# 04_-FT601_USB_Tx_Rx_Interface.net
KiCad netlist of a schematic drawn in Altium Designer
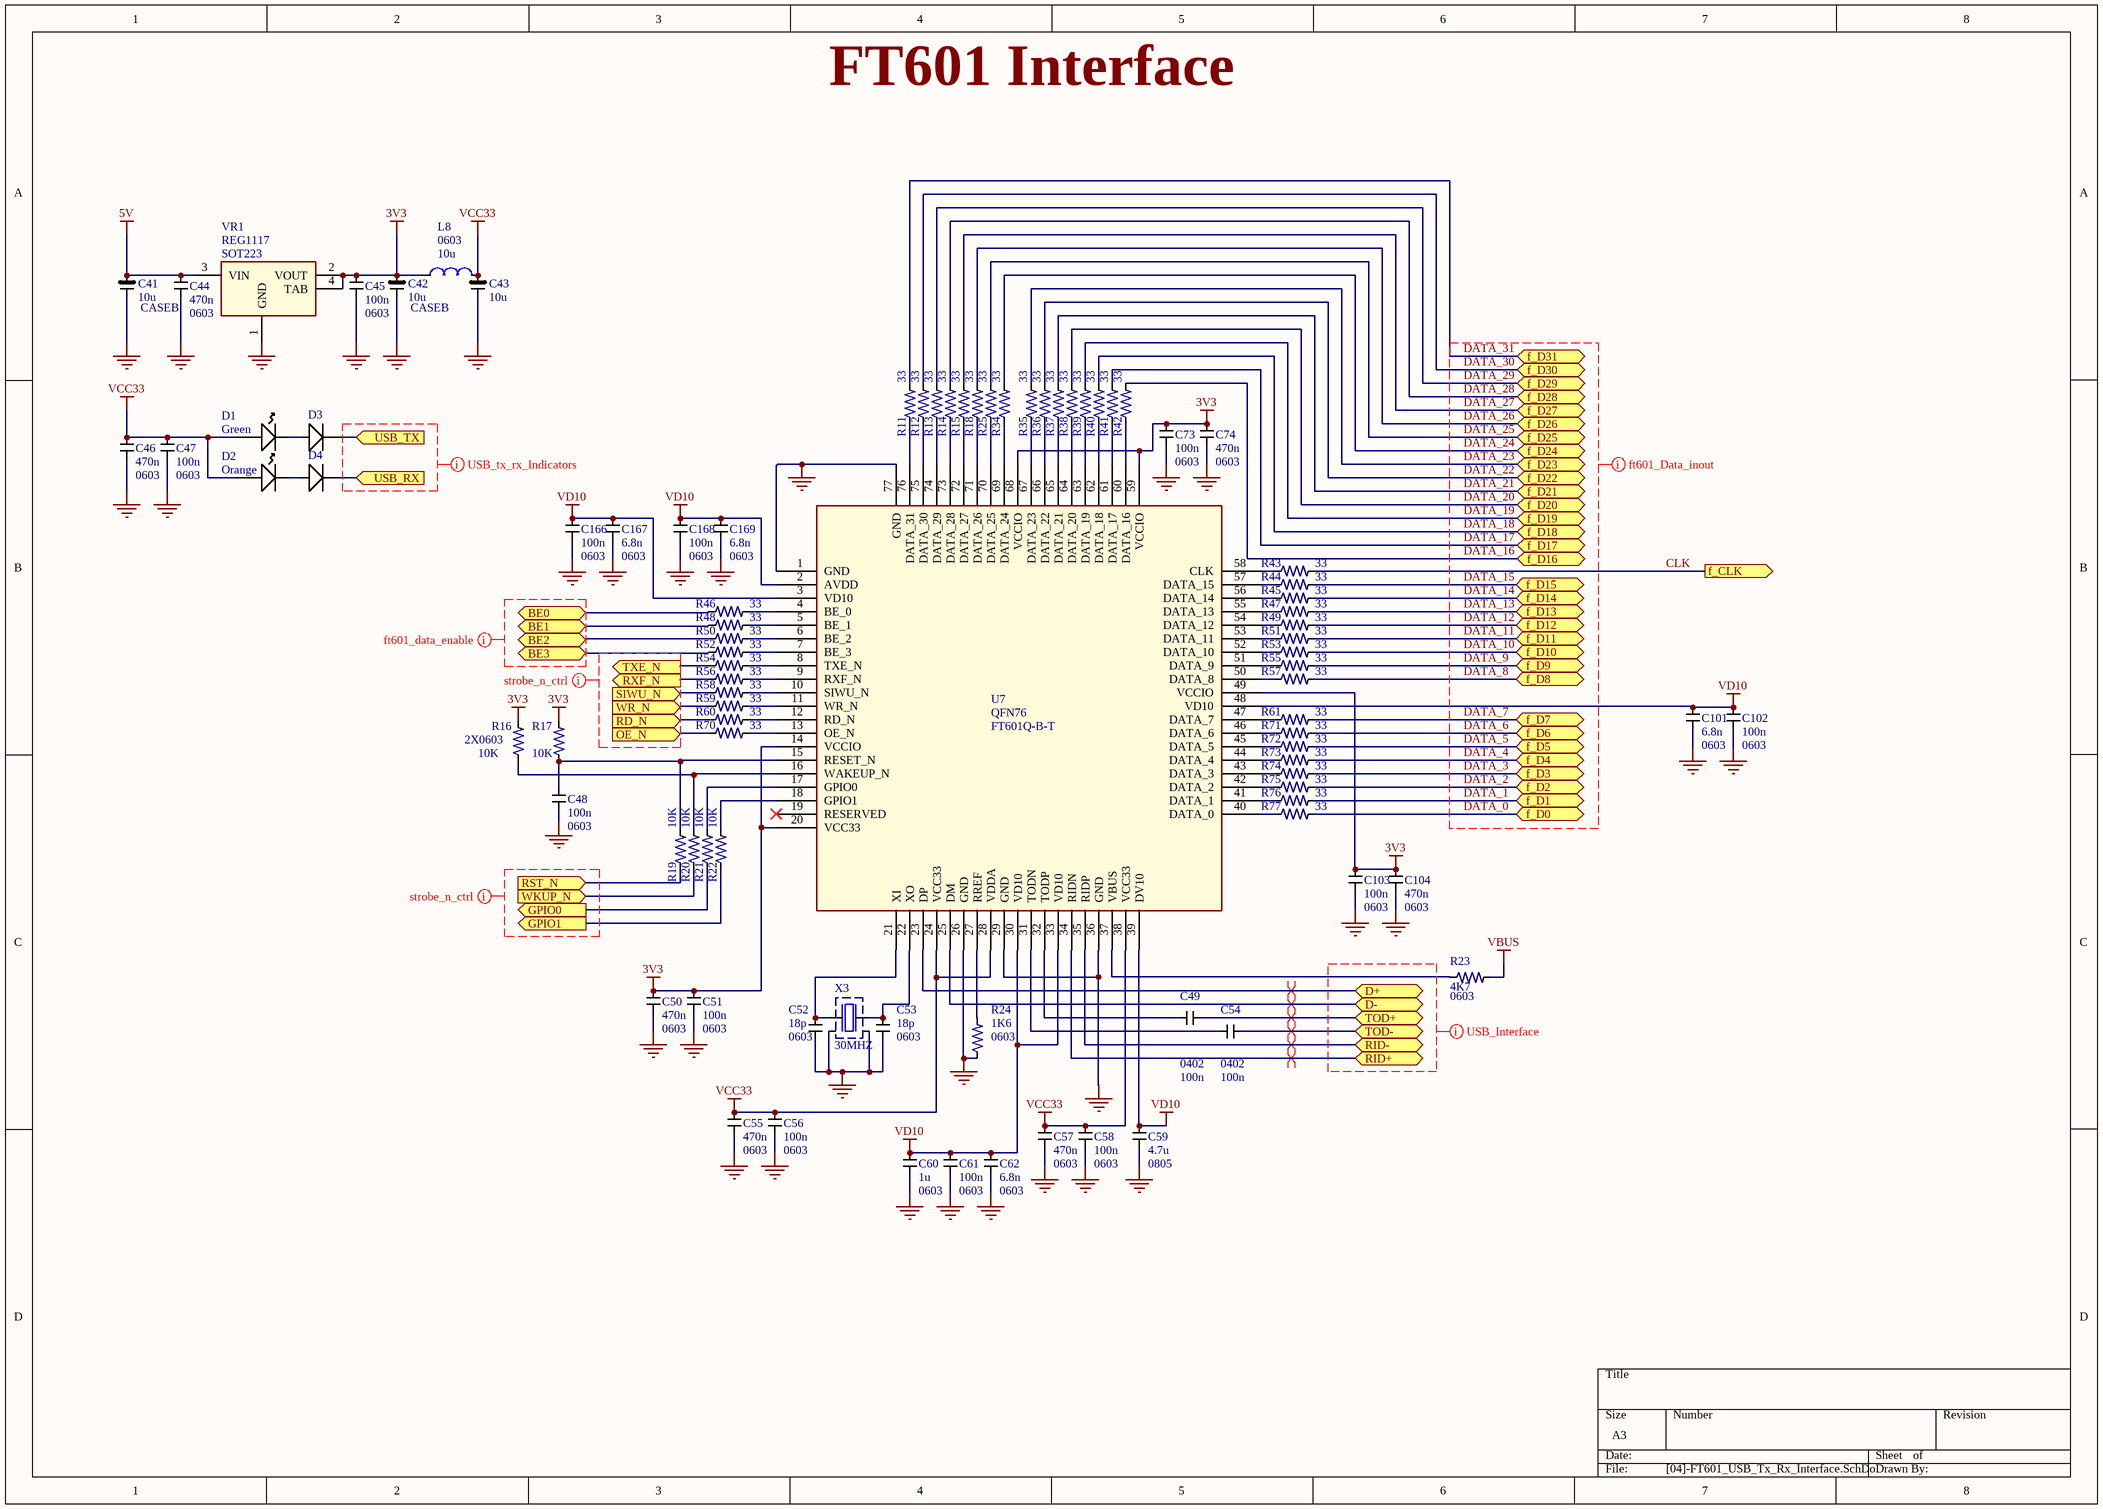
[diagram p0: [04]-FT601_USB_Tx_Rx_Interface.SchDoc]

(export (version "E")
  (design (tool "Eeschema 10.0.6"))
  (components
    (comp (ref "C41")
      (value "10u")
      (footprint "CAPC3528X21N")
      (fields (field (name "PCB LAYER") "CASEB"))
      (libsource (lib "T495B106K010ATE600") (part "Component_1"))
    )
    (comp (ref "C42")
      (value "10u")
      (footprint "CAPC3528X21N")
      (fields (field (name "PCB LAYER") "CASEB"))
      (libsource (lib "T495B106K010ATE600") (part "Component_1"))
    )
    (comp (ref "C43")
      (value "10u")
      (footprint "CAPC3528X21N")
      (libsource (lib "T495B106K010ATE600") (part "Component_1"))
    )
    (comp (ref "C44")
      (value "470n")
      (fields (field (name "PCB FOOTPRINT") "0603"))
      (libsource (lib "06031C104KAT2A") (part "Component_1"))
    )
    (comp (ref "C45")
      (value "100n")
      (fields (field (name "PCB FOOTPRINT") "0603"))
      (libsource (lib "06031C104KAT2A") (part "Component_1"))
    )
    (comp (ref "C46")
      (value "470n")
      (fields (field (name "PCB FOOTPRINT") "0603"))
      (libsource (lib "06031C104KAT2A") (part "Component_1"))
    )
    (comp (ref "C47")
      (value "100n")
      (fields (field (name "PCB FOOTPRINT") "0603"))
      (libsource (lib "06031C104KAT2A") (part "Component_1"))
    )
    (comp (ref "C48")
      (value "100n")
      (fields (field (name "PCB FOOTPRINT") "0603"))
      (libsource (lib "06031C104KAT2A") (part "Component_1"))
    )
    (comp (ref "C49")
      (value "100n")
      (footprint "*CAPC1005X60N")
      (fields (field (name "PCB STAKE") "0402"))
      (libsource (lib "04023C104KAT2A_0402") (part "Component_1"))
    )
    (comp (ref "C50")
      (value "470n")
      (fields (field (name "PCB FOOTPRINT") "0603"))
      (libsource (lib "06031C104KAT2A") (part "Component_1"))
    )
    (comp (ref "C51")
      (value "100n")
      (fields (field (name "PCB FOOTPRINT") "0603"))
      (libsource (lib "06031C104KAT2A") (part "Component_1"))
    )
    (comp (ref "C52")
      (value "18p")
      (footprint "*CAPC1608X90")
      (fields (field (name "PCB LAYOUT:") "0603"))
      (libsource (lib "06032U180GAT2A") (part "Component_1"))
    )
    (comp (ref "C53")
      (value "18p")
      (footprint "*CAPC1608X90")
      (fields (field (name "PCB LAYOUT:") "0603"))
      (libsource (lib "06032U180GAT2A") (part "Component_1"))
    )
    (comp (ref "C54")
      (value "100n")
      (footprint "*CAPC1005X60N")
      (fields (field (name "PCB STAKE") "0402"))
      (libsource (lib "04023C104KAT2A_0402") (part "Component_1"))
    )
    (comp (ref "C55")
      (value "470n")
      (fields (field (name "PCB FOOTPRINT") "0603"))
      (libsource (lib "06031C104KAT2A") (part "Component_1"))
    )
    (comp (ref "C56")
      (value "100n")
      (fields (field (name "PCB FOOTPRINT") "0603"))
      (libsource (lib "06031C104KAT2A") (part "Component_1"))
    )
    (comp (ref "C57")
      (value "470n")
      (fields (field (name "PCB FOOTPRINT") "0603"))
      (libsource (lib "06031C104KAT2A") (part "Component_1"))
    )
    (comp (ref "C58")
      (value "100n")
      (fields (field (name "PCB FOOTPRINT") "0603"))
      (libsource (lib "06031C104KAT2A") (part "Component_1"))
    )
    (comp (ref "C59")
      (value "4.7u")
      (footprint "*CAPC2013X140N")
      (fields (field (name "PCB PACKAGE") "0805"))
      (libsource (lib "08053D475KAT2A") (part "Component_1"))
    )
    (comp (ref "C60")
      (value "1u")
      (fields (field (name "PCB FOOTPRINT") "0603"))
      (libsource (lib "06031C104KAT2A") (part "Component_1"))
    )
    (comp (ref "C61")
      (value "100n")
      (footprint "CAPC1608X10N")
      (fields (field (name "PCB PACKAGE") "0603"))
      (libsource (lib "MC0603B682K500CT") (part "Component_1"))
    )
    (comp (ref "C62")
      (value "6.8n")
      (footprint "*0603")
      (fields (field (name "PCB LAYER:") "0603"))
      (libsource (lib "0603YC105KAT2A") (part "Component_1"))
    )
    (comp (ref "C73")
      (value "100n")
      (fields (field (name "PCB FOOTPRINT") "0603"))
      (libsource (lib "06031C104KAT2A") (part "Component_1"))
    )
    (comp (ref "C74")
      (value "470n")
      (fields (field (name "PCB FOOTPRINT") "0603"))
      (libsource (lib "06031C104KAT2A") (part "Component_1"))
    )
    (comp (ref "C101")
      (value "6.8n")
      (footprint "CAPC1608X10N")
      (fields (field (name "PCB PACKAGE") "0603"))
      (libsource (lib "MC0603B682K500CT") (part "Component_1"))
    )
    (comp (ref "C102")
      (value "100n")
      (fields (field (name "PCB FOOTPRINT") "0603"))
      (libsource (lib "06031C104KAT2A") (part "Component_1"))
    )
    (comp (ref "C103")
      (value "100n")
      (fields (field (name "PCB FOOTPRINT") "0603"))
      (libsource (lib "06031C104KAT2A") (part "Component_1"))
    )
    (comp (ref "C104")
      (value "470n")
      (fields (field (name "PCB FOOTPRINT") "0603"))
      (libsource (lib "06031C104KAT2A") (part "Component_1"))
    )
    (comp (ref "C166")
      (value "100n")
      (fields (field (name "PCB FOOTPRINT") "0603"))
      (libsource (lib "06031C104KAT2A") (part "Component_1"))
    )
    (comp (ref "C167")
      (value "6.8n")
      (fields (field (name "PCB FOOTPRINT") "0603"))
      (libsource (lib "06031C104KAT2A") (part "Component_1"))
    )
    (comp (ref "C168")
      (value "100n")
      (fields (field (name "PCB FOOTPRINT") "0603"))
      (libsource (lib "06031C104KAT2A") (part "Component_1"))
    )
    (comp (ref "C169")
      (value "6.8n")
      (fields (field (name "PCB FOOTPRINT") "0603"))
      (libsource (lib "06031C104KAT2A") (part "Component_1"))
    )
    (comp (ref "D1")
      (value "Kingbright Green LED, 70 mcd 120 ° 0805")
      (footprint "LED1913X12NGREEN")
      (fields
        (field (name "MANUFACTURER") "KingBright")
        (field (name "MANUFACTURER PART NO.") "KP-2012MGC")
        (field (name "COLOR") "Green")
        (field (name "CREATOR") "Ritesh Kanjee")
      )
      (libsource (lib "KingBright LEDs") (part "Kingbright Green LED, 70 mcd 120 ° 0805"))
    )
    (comp (ref "D2")
      (value "Kingbright Orange LED, 200 mcd 120 ° 0805")
      (footprint "LED1913X12NYEL/ORANGE")
      (fields
        (field (name "MANUFACTURER") "KingBright")
        (field (name "MANUFACTURER PART NO.") "KP-2012SEC")
        (field (name "COLOR") "Orange")
        (field (name "CREATOR") "Ritesh Kanjee")
      )
      (libsource (lib "KingBright LEDs") (part "Kingbright Orange LED, 200 mcd 120 ° 0805"))
    )
    (comp (ref "D3")
      (value "Panasonic DB2J20900L Schottky Diode, 0.5A, 20V, 2.4ns, 2-Pin SMini2 F5 B")
      (footprint "DIOM1712X07N")
      (fields
        (field (name "MANUFACTURER") "Panasonic")
        (field (name "MANUFACTURER PART NO.") "DB2J20900L")
        (field (name "CREATED BY") "R Kanjee")
      )
      (libsource (lib "Panasonic Diodes") (part "Schottky Diode, 0.5A, 20V, 2.4ns, 2-Pin SMini2 F5 B"))
    )
    (comp (ref "D4")
      (value "Panasonic DB2J20900L Schottky Diode, 0.5A, 20V, 2.4ns, 2-Pin SMini2 F5 B")
      (footprint "DIOM1712X07N")
      (fields
        (field (name "MANUFACTURER") "Panasonic")
        (field (name "MANUFACTURER PART NO.") "DB2J20900L")
        (field (name "CREATED BY") "R Kanjee")
      )
      (libsource (lib "Panasonic Diodes") (part "Schottky Diode, 0.5A, 20V, 2.4ns, 2-Pin SMini2 F5 B"))
    )
    (comp (ref "L8")
      (value "10u")
      (footprint "*INDC1608X95N")
      (fields (field (name "PCB LAYOUT:") "0603"))
      (libsource (lib "MLZ1608M100WTD25") (part "Component_1"))
    )
    (comp (ref "R11")
      (value "33")
      (footprint "*R0402")
      (description "Res Thin Film 0603 76.8 Ohm 0.1% 1/10W Â±15ppm/Â°C Molded SMD Paper T/R")
      (libsource (lib "SMD-RES-100K-1_-1_16W_0402_") (part "RP73D1J76R8BTDG"))
    )
    (comp (ref "R12")
      (value "33")
      (footprint "*R0402")
      (description "Res Thin Film 0603 76.8 Ohm 0.1% 1/10W Â±15ppm/Â°C Molded SMD Paper T/R")
      (libsource (lib "SMD-RES-100K-1_-1_16W_0402_") (part "RP73D1J76R8BTDG"))
    )
    (comp (ref "R13")
      (value "33")
      (footprint "*R0402")
      (description "Res Thin Film 0603 76.8 Ohm 0.1% 1/10W Â±15ppm/Â°C Molded SMD Paper T/R")
      (libsource (lib "SMD-RES-100K-1_-1_16W_0402_") (part "RP73D1J76R8BTDG"))
    )
    (comp (ref "R14")
      (value "33")
      (footprint "*R0402")
      (description "Res Thin Film 0603 76.8 Ohm 0.1% 1/10W Â±15ppm/Â°C Molded SMD Paper T/R")
      (libsource (lib "SMD-RES-100K-1_-1_16W_0402_") (part "RP73D1J76R8BTDG"))
    )
    (comp (ref "R15")
      (value "33")
      (footprint "*R0402")
      (description "Res Thin Film 0603 76.8 Ohm 0.1% 1/10W Â±15ppm/Â°C Molded SMD Paper T/R")
      (libsource (lib "SMD-RES-100K-1_-1_16W_0402_") (part "RP73D1J76R8BTDG"))
    )
    (comp (ref "R16")
      (value "10K")
      (footprint "*0603")
      (description "Res Thin Film 0603 76.8 Ohm 0.1% 1/10W Â±15ppm/Â°C Molded SMD Paper T/R")
      (fields
        (field (name "MP") "RP73D1J76R8BTDG")
        (field (name "MF") "TE Connectivity / Holsworthy")
        (field (name "FOOT PRINT") "2X0603")
      )
      (libsource (lib "CRCW060310K0FKEAHP") (part "RP73D1J76R8BTDG"))
    )
    (comp (ref "R17")
      (value "10K")
      (footprint "*0603")
      (description "Res Thin Film 0603 76.8 Ohm 0.1% 1/10W Â±15ppm/Â°C Molded SMD Paper T/R")
      (fields (field (name "MP") "RP73D1J76R8BTDG") (field (name "MF") "TE Connectivity / Holsworthy"))
      (libsource (lib "CRCW060310K0FKEAHP") (part "RP73D1J76R8BTDG"))
    )
    (comp (ref "R18")
      (value "33")
      (footprint "*R0402")
      (description "Res Thin Film 0603 76.8 Ohm 0.1% 1/10W Â±15ppm/Â°C Molded SMD Paper T/R")
      (libsource (lib "SMD-RES-100K-1_-1_16W_0402_") (part "RP73D1J76R8BTDG"))
    )
    (comp (ref "R19")
      (value "10K")
      (footprint "*0603")
      (description "Res Thin Film 0603 76.8 Ohm 0.1% 1/10W Â±15ppm/Â°C Molded SMD Paper T/R")
      (fields (field (name "MP") "RP73D1J76R8BTDG") (field (name "MF") "TE Connectivity / Holsworthy"))
      (libsource (lib "CRCW060310K0FKEAHP") (part "RP73D1J76R8BTDG"))
    )
    (comp (ref "R20")
      (value "10K")
      (footprint "*0603")
      (description "Res Thin Film 0603 76.8 Ohm 0.1% 1/10W Â±15ppm/Â°C Molded SMD Paper T/R")
      (fields (field (name "MP") "RP73D1J76R8BTDG") (field (name "MF") "TE Connectivity / Holsworthy"))
      (libsource (lib "CRCW060310K0FKEAHP") (part "RP73D1J76R8BTDG"))
    )
    (comp (ref "R21")
      (value "10K")
      (footprint "*0603")
      (description "Res Thin Film 0603 76.8 Ohm 0.1% 1/10W Â±15ppm/Â°C Molded SMD Paper T/R")
      (fields (field (name "MP") "RP73D1J76R8BTDG") (field (name "MF") "TE Connectivity / Holsworthy"))
      (libsource (lib "CRCW060310K0FKEAHP") (part "RP73D1J76R8BTDG"))
    )
    (comp (ref "R22")
      (value "10K")
      (footprint "*0603")
      (description "Res Thin Film 0603 76.8 Ohm 0.1% 1/10W Â±15ppm/Â°C Molded SMD Paper T/R")
      (fields (field (name "MP") "RP73D1J76R8BTDG") (field (name "MF") "TE Connectivity / Holsworthy"))
      (libsource (lib "CRCW060310K0FKEAHP") (part "RP73D1J76R8BTDG"))
    )
    (comp (ref "R23")
      (value "4K7")
      (footprint "*RESC1608X50N")
      (description "Res Thin Film 0603 76.8 Ohm 0.1% 1/10W Â±15ppm/Â°C Molded SMD Paper T/R")
      (fields
        (field (name "MP") "RP73D1J76R8BTDG")
        (field (name "MF") "TE Connectivity / Holsworthy")
        (field (name "FOOT PRINT") "0603")
      )
      (libsource (lib "CRGH0603F4K7") (part "RP73D1J76R8BTDG"))
    )
    (comp (ref "R24")
      (value "1K6")
      (footprint "*0603")
      (description "Res Thin Film 0603 76.8 Ohm 0.1% 1/10W Â±15ppm/Â°C Molded SMD Paper T/R")
      (fields
        (field (name "MP") "RP73D1J76R8BTDG")
        (field (name "MF") "TE Connectivity / Holsworthy")
        (field (name "FOOT PRINT") "0603")
      )
      (libsource (lib "CRCW060310K0FKEAHP") (part "RP73D1J76R8BTDG"))
    )
    (comp (ref "R25")
      (value "33")
      (footprint "*R0402")
      (description "Res Thin Film 0603 76.8 Ohm 0.1% 1/10W Â±15ppm/Â°C Molded SMD Paper T/R")
      (libsource (lib "SMD-RES-100K-1_-1_16W_0402_") (part "RP73D1J76R8BTDG"))
    )
    (comp (ref "R34")
      (value "33")
      (footprint "*R0402")
      (description "Res Thin Film 0603 76.8 Ohm 0.1% 1/10W Â±15ppm/Â°C Molded SMD Paper T/R")
      (libsource (lib "SMD-RES-100K-1_-1_16W_0402_") (part "RP73D1J76R8BTDG"))
    )
    (comp (ref "R35")
      (value "33")
      (footprint "*R0402")
      (description "Res Thin Film 0603 76.8 Ohm 0.1% 1/10W Â±15ppm/Â°C Molded SMD Paper T/R")
      (libsource (lib "SMD-RES-100K-1_-1_16W_0402_") (part "RP73D1J76R8BTDG"))
    )
    (comp (ref "R36")
      (value "33")
      (footprint "*R0402")
      (description "Res Thin Film 0603 76.8 Ohm 0.1% 1/10W Â±15ppm/Â°C Molded SMD Paper T/R")
      (libsource (lib "SMD-RES-100K-1_-1_16W_0402_") (part "RP73D1J76R8BTDG"))
    )
    (comp (ref "R37")
      (value "33")
      (footprint "*R0402")
      (description "Res Thin Film 0603 76.8 Ohm 0.1% 1/10W Â±15ppm/Â°C Molded SMD Paper T/R")
      (libsource (lib "SMD-RES-100K-1_-1_16W_0402_") (part "RP73D1J76R8BTDG"))
    )
    (comp (ref "R38")
      (value "33")
      (footprint "*R0402")
      (description "Res Thin Film 0603 76.8 Ohm 0.1% 1/10W Â±15ppm/Â°C Molded SMD Paper T/R")
      (libsource (lib "SMD-RES-100K-1_-1_16W_0402_") (part "RP73D1J76R8BTDG"))
    )
    (comp (ref "R39")
      (value "33")
      (footprint "*R0402")
      (description "Res Thin Film 0603 76.8 Ohm 0.1% 1/10W Â±15ppm/Â°C Molded SMD Paper T/R")
      (libsource (lib "SMD-RES-100K-1_-1_16W_0402_") (part "RP73D1J76R8BTDG"))
    )
    (comp (ref "R40")
      (value "33")
      (footprint "*R0402")
      (description "Res Thin Film 0603 76.8 Ohm 0.1% 1/10W Â±15ppm/Â°C Molded SMD Paper T/R")
      (libsource (lib "SMD-RES-100K-1_-1_16W_0402_") (part "RP73D1J76R8BTDG"))
    )
    (comp (ref "R41")
      (value "33")
      (footprint "*R0402")
      (description "Res Thin Film 0603 76.8 Ohm 0.1% 1/10W Â±15ppm/Â°C Molded SMD Paper T/R")
      (libsource (lib "SMD-RES-100K-1_-1_16W_0402_") (part "RP73D1J76R8BTDG"))
    )
    (comp (ref "R42")
      (value "33")
      (footprint "*R0402")
      (description "Res Thin Film 0603 76.8 Ohm 0.1% 1/10W Â±15ppm/Â°C Molded SMD Paper T/R")
      (libsource (lib "SMD-RES-100K-1_-1_16W_0402_") (part "RP73D1J76R8BTDG"))
    )
    (comp (ref "R43")
      (value "33")
      (footprint "*R0402")
      (description "Res Thin Film 0603 76.8 Ohm 0.1% 1/10W Â±15ppm/Â°C Molded SMD Paper T/R")
      (libsource (lib "SMD-RES-100K-1_-1_16W_0402_") (part "RP73D1J76R8BTDG"))
    )
    (comp (ref "R44")
      (value "33")
      (footprint "*R0402")
      (description "Res Thin Film 0603 76.8 Ohm 0.1% 1/10W Â±15ppm/Â°C Molded SMD Paper T/R")
      (libsource (lib "SMD-RES-100K-1_-1_16W_0402_") (part "RP73D1J76R8BTDG"))
    )
    (comp (ref "R45")
      (value "33")
      (footprint "*R0402")
      (description "Res Thin Film 0603 76.8 Ohm 0.1% 1/10W Â±15ppm/Â°C Molded SMD Paper T/R")
      (libsource (lib "SMD-RES-100K-1_-1_16W_0402_") (part "RP73D1J76R8BTDG"))
    )
    (comp (ref "R46")
      (value "33")
      (footprint "*R0402")
      (description "Res Thin Film 0603 76.8 Ohm 0.1% 1/10W Â±15ppm/Â°C Molded SMD Paper T/R")
      (libsource (lib "SMD-RES-100K-1_-1_16W_0402_") (part "RP73D1J76R8BTDG"))
    )
    (comp (ref "R47")
      (value "33")
      (footprint "*R0402")
      (description "Res Thin Film 0603 76.8 Ohm 0.1% 1/10W Â±15ppm/Â°C Molded SMD Paper T/R")
      (libsource (lib "SMD-RES-100K-1_-1_16W_0402_") (part "RP73D1J76R8BTDG"))
    )
    (comp (ref "R48")
      (value "33")
      (footprint "*R0402")
      (description "Res Thin Film 0603 76.8 Ohm 0.1% 1/10W Â±15ppm/Â°C Molded SMD Paper T/R")
      (libsource (lib "SMD-RES-100K-1_-1_16W_0402_") (part "RP73D1J76R8BTDG"))
    )
    (comp (ref "R49")
      (value "33")
      (footprint "*R0402")
      (description "Res Thin Film 0603 76.8 Ohm 0.1% 1/10W Â±15ppm/Â°C Molded SMD Paper T/R")
      (libsource (lib "SMD-RES-100K-1_-1_16W_0402_") (part "RP73D1J76R8BTDG"))
    )
    (comp (ref "R50")
      (value "33")
      (footprint "*R0402")
      (description "Res Thin Film 0603 76.8 Ohm 0.1% 1/10W Â±15ppm/Â°C Molded SMD Paper T/R")
      (libsource (lib "SMD-RES-100K-1_-1_16W_0402_") (part "RP73D1J76R8BTDG"))
    )
    (comp (ref "R51")
      (value "33")
      (footprint "*R0402")
      (description "Res Thin Film 0603 76.8 Ohm 0.1% 1/10W Â±15ppm/Â°C Molded SMD Paper T/R")
      (libsource (lib "SMD-RES-100K-1_-1_16W_0402_") (part "RP73D1J76R8BTDG"))
    )
    (comp (ref "R52")
      (value "33")
      (footprint "*R0402")
      (description "Res Thin Film 0603 76.8 Ohm 0.1% 1/10W Â±15ppm/Â°C Molded SMD Paper T/R")
      (libsource (lib "SMD-RES-100K-1_-1_16W_0402_") (part "RP73D1J76R8BTDG"))
    )
    (comp (ref "R53")
      (value "33")
      (footprint "*R0402")
      (description "Res Thin Film 0603 76.8 Ohm 0.1% 1/10W Â±15ppm/Â°C Molded SMD Paper T/R")
      (libsource (lib "SMD-RES-100K-1_-1_16W_0402_") (part "RP73D1J76R8BTDG"))
    )
    (comp (ref "R54")
      (value "33")
      (footprint "*R0402")
      (description "Res Thin Film 0603 76.8 Ohm 0.1% 1/10W Â±15ppm/Â°C Molded SMD Paper T/R")
      (libsource (lib "SMD-RES-100K-1_-1_16W_0402_") (part "RP73D1J76R8BTDG"))
    )
    (comp (ref "R55")
      (value "33")
      (footprint "*R0402")
      (description "Res Thin Film 0603 76.8 Ohm 0.1% 1/10W Â±15ppm/Â°C Molded SMD Paper T/R")
      (libsource (lib "SMD-RES-100K-1_-1_16W_0402_") (part "RP73D1J76R8BTDG"))
    )
    (comp (ref "R56")
      (value "33")
      (footprint "*R0402")
      (description "Res Thin Film 0603 76.8 Ohm 0.1% 1/10W Â±15ppm/Â°C Molded SMD Paper T/R")
      (libsource (lib "SMD-RES-100K-1_-1_16W_0402_") (part "RP73D1J76R8BTDG"))
    )
    (comp (ref "R57")
      (value "33")
      (footprint "*R0402")
      (description "Res Thin Film 0603 76.8 Ohm 0.1% 1/10W Â±15ppm/Â°C Molded SMD Paper T/R")
      (libsource (lib "SMD-RES-100K-1_-1_16W_0402_") (part "RP73D1J76R8BTDG"))
    )
    (comp (ref "R58")
      (value "33")
      (footprint "*R0402")
      (description "Res Thin Film 0603 76.8 Ohm 0.1% 1/10W Â±15ppm/Â°C Molded SMD Paper T/R")
      (libsource (lib "SMD-RES-100K-1_-1_16W_0402_") (part "RP73D1J76R8BTDG"))
    )
    (comp (ref "R59")
      (value "33")
      (footprint "*R0402")
      (description "Res Thin Film 0603 76.8 Ohm 0.1% 1/10W Â±15ppm/Â°C Molded SMD Paper T/R")
      (libsource (lib "SMD-RES-100K-1_-1_16W_0402_") (part "RP73D1J76R8BTDG"))
    )
    (comp (ref "R60")
      (value "33")
      (footprint "*R0402")
      (description "Res Thin Film 0603 76.8 Ohm 0.1% 1/10W Â±15ppm/Â°C Molded SMD Paper T/R")
      (libsource (lib "SMD-RES-100K-1_-1_16W_0402_") (part "RP73D1J76R8BTDG"))
    )
    (comp (ref "R61")
      (value "33")
      (footprint "*R0402")
      (description "Res Thin Film 0603 76.8 Ohm 0.1% 1/10W Â±15ppm/Â°C Molded SMD Paper T/R")
      (libsource (lib "SMD-RES-100K-1_-1_16W_0402_") (part "RP73D1J76R8BTDG"))
    )
    (comp (ref "R70")
      (value "33")
      (footprint "*R0402")
      (description "Res Thin Film 0603 76.8 Ohm 0.1% 1/10W Â±15ppm/Â°C Molded SMD Paper T/R")
      (libsource (lib "SMD-RES-100K-1_-1_16W_0402_") (part "RP73D1J76R8BTDG"))
    )
    (comp (ref "R71")
      (value "33")
      (footprint "*R0402")
      (description "Res Thin Film 0603 76.8 Ohm 0.1% 1/10W Â±15ppm/Â°C Molded SMD Paper T/R")
      (libsource (lib "SMD-RES-100K-1_-1_16W_0402_") (part "RP73D1J76R8BTDG"))
    )
    (comp (ref "R72")
      (value "33")
      (footprint "*R0402")
      (description "Res Thin Film 0603 76.8 Ohm 0.1% 1/10W Â±15ppm/Â°C Molded SMD Paper T/R")
      (libsource (lib "SMD-RES-100K-1_-1_16W_0402_") (part "RP73D1J76R8BTDG"))
    )
    (comp (ref "R73")
      (value "33")
      (footprint "*R0402")
      (description "Res Thin Film 0603 76.8 Ohm 0.1% 1/10W Â±15ppm/Â°C Molded SMD Paper T/R")
      (libsource (lib "SMD-RES-100K-1_-1_16W_0402_") (part "RP73D1J76R8BTDG"))
    )
    (comp (ref "R74")
      (value "33")
      (footprint "*R0402")
      (description "Res Thin Film 0603 76.8 Ohm 0.1% 1/10W Â±15ppm/Â°C Molded SMD Paper T/R")
      (libsource (lib "SMD-RES-100K-1_-1_16W_0402_") (part "RP73D1J76R8BTDG"))
    )
    (comp (ref "R75")
      (value "33")
      (footprint "*R0402")
      (description "Res Thin Film 0603 76.8 Ohm 0.1% 1/10W Â±15ppm/Â°C Molded SMD Paper T/R")
      (libsource (lib "SMD-RES-100K-1_-1_16W_0402_") (part "RP73D1J76R8BTDG"))
    )
    (comp (ref "R76")
      (value "33")
      (footprint "*R0402")
      (description "Res Thin Film 0603 76.8 Ohm 0.1% 1/10W Â±15ppm/Â°C Molded SMD Paper T/R")
      (libsource (lib "SMD-RES-100K-1_-1_16W_0402_") (part "RP73D1J76R8BTDG"))
    )
    (comp (ref "R77")
      (value "33")
      (footprint "*R0402")
      (description "Res Thin Film 0603 76.8 Ohm 0.1% 1/10W Â±15ppm/Â°C Molded SMD Paper T/R")
      (libsource (lib "SMD-RES-100K-1_-1_16W_0402_") (part "RP73D1J76R8BTDG"))
    )
    (comp (ref "U7")
      (value "FT601Q-B-T")
      (footprint "QFN40P900X900X100-77N")
      (description "USB3.0 to 32bit FIFO Interface Bridge QFN76 Tray")
      (fields
        (field (name "PACKAGE TYPE:") "QFN76")
        (field (name "DESIGNER") "Faheem Minhas")
        (field (name "DATA CREATED") "21-Janruary-2019")
      )
      (libsource (lib "FT601Q-B-T") (part "FT601Q-B-T"))
    )
    (comp (ref "VR1")
      (value "REG1117")
      (footprint "*SOT223")
      (description "LDO Regulator Pos 1.25V to 13.5V 0.8A 4-Pin_3+Tab_ SOT-223 Tube")
      (fields
        (field (name "MF") "Texas Instruments")
        (field (name "DIGI-KEY_PART_NUMBER") "REG1117-ND")
        (field (name "PCB LAYOUT:") "SOT223")
      )
      (libsource (lib "REG1117") (part "REG1117"))
    )
    (comp (ref "X3")
      (value "30MHZ")
      (footprint "OSC_DSC6083CI2A-032K768")
      (fields (field (name "MF") "ABM8G-30.000MHZ-18-D2Y-T"))
      (libsource (lib "ABM8G-30.000MHZ-18-D2Y-T") (part "Component_1"))
    )
  )
  (nets
    (net (code "1") (name "/BE0") (class "Default")
      (node (ref "R46") (pin "1") (pinfunction "1_1") (pintype "passive"))
    )
    (net (code "2") (name "/BE1") (class "Default")
      (node (ref "R48") (pin "1") (pinfunction "1_1") (pintype "passive"))
    )
    (net (code "3") (name "/BE2") (class "Default")
      (node (ref "R50") (pin "1") (pinfunction "1_1") (pintype "passive"))
    )
    (net (code "4") (name "/BE3") (class "Default")
      (node (ref "R52") (pin "1") (pinfunction "1_1") (pintype "passive"))
    )
    (net (code "5") (name "/CLK") (class "Default")
      (node (ref "R43") (pin "2") (pinfunction "2_2") (pintype "passive"))
    )
    (net (code "6") (name "/D+") (class "Default")
      (node (ref "U7") (pin "23") (pinfunction "DP_23") (pintype "passive"))
    )
    (net (code "7") (name "/D-") (class "Default")
      (node (ref "U7") (pin "25") (pinfunction "DM_25") (pintype "passive"))
    )
    (net (code "8") (name "/DATA_0") (class "Default")
      (node (ref "R77") (pin "2") (pinfunction "2_2") (pintype "passive"))
    )
    (net (code "9") (name "/DATA_1") (class "Default")
      (node (ref "R76") (pin "2") (pinfunction "2_2") (pintype "passive"))
    )
    (net (code "10") (name "/DATA_2") (class "Default")
      (node (ref "R75") (pin "2") (pinfunction "2_2") (pintype "passive"))
    )
    (net (code "11") (name "/DATA_3") (class "Default")
      (node (ref "R74") (pin "2") (pinfunction "2_2") (pintype "passive"))
    )
    (net (code "12") (name "/DATA_4") (class "Default")
      (node (ref "R73") (pin "2") (pinfunction "2_2") (pintype "passive"))
    )
    (net (code "13") (name "/DATA_5") (class "Default")
      (node (ref "R72") (pin "2") (pinfunction "2_2") (pintype "passive"))
    )
    (net (code "14") (name "/DATA_6") (class "Default")
      (node (ref "R71") (pin "2") (pinfunction "2_2") (pintype "passive"))
    )
    (net (code "15") (name "/DATA_7") (class "Default")
      (node (ref "R61") (pin "2") (pinfunction "2_2") (pintype "passive"))
    )
    (net (code "16") (name "/DATA_8") (class "Default")
      (node (ref "R57") (pin "2") (pinfunction "2_2") (pintype "passive"))
    )
    (net (code "17") (name "/DATA_9") (class "Default")
      (node (ref "R55") (pin "2") (pinfunction "2_2") (pintype "passive"))
    )
    (net (code "18") (name "/DATA_10") (class "Default")
      (node (ref "R53") (pin "2") (pinfunction "2_2") (pintype "passive"))
    )
    (net (code "19") (name "/DATA_11") (class "Default")
      (node (ref "R51") (pin "2") (pinfunction "2_2") (pintype "passive"))
    )
    (net (code "20") (name "/DATA_12") (class "Default")
      (node (ref "R49") (pin "2") (pinfunction "2_2") (pintype "passive"))
    )
    (net (code "21") (name "/DATA_13") (class "Default")
      (node (ref "R47") (pin "2") (pinfunction "2_2") (pintype "passive"))
    )
    (net (code "22") (name "/DATA_14") (class "Default")
      (node (ref "R45") (pin "2") (pinfunction "2_2") (pintype "passive"))
    )
    (net (code "23") (name "/DATA_15") (class "Default")
      (node (ref "R44") (pin "2") (pinfunction "2_2") (pintype "passive"))
    )
    (net (code "24") (name "/DATA_16") (class "Default")
      (node (ref "R42") (pin "2") (pinfunction "2_2") (pintype "passive"))
    )
    (net (code "25") (name "/DATA_17") (class "Default")
      (node (ref "R41") (pin "2") (pinfunction "2_2") (pintype "passive"))
    )
    (net (code "26") (name "/DATA_18") (class "Default")
      (node (ref "R40") (pin "2") (pinfunction "2_2") (pintype "passive"))
    )
    (net (code "27") (name "/DATA_19") (class "Default")
      (node (ref "R39") (pin "2") (pinfunction "2_2") (pintype "passive"))
    )
    (net (code "28") (name "/DATA_20") (class "Default")
      (node (ref "R38") (pin "2") (pinfunction "2_2") (pintype "passive"))
    )
    (net (code "29") (name "/DATA_21") (class "Default")
      (node (ref "R37") (pin "2") (pinfunction "2_2") (pintype "passive"))
    )
    (net (code "30") (name "/DATA_22") (class "Default")
      (node (ref "R36") (pin "2") (pinfunction "2_2") (pintype "passive"))
    )
    (net (code "31") (name "/DATA_23") (class "Default")
      (node (ref "R35") (pin "2") (pinfunction "2_2") (pintype "passive"))
    )
    (net (code "32") (name "/DATA_24") (class "Default")
      (node (ref "R34") (pin "2") (pinfunction "2_2") (pintype "passive"))
    )
    (net (code "33") (name "/DATA_25") (class "Default")
      (node (ref "R25") (pin "2") (pinfunction "2_2") (pintype "passive"))
    )
    (net (code "34") (name "/DATA_26") (class "Default")
      (node (ref "R18") (pin "2") (pinfunction "2_2") (pintype "passive"))
    )
    (net (code "35") (name "/DATA_27") (class "Default")
      (node (ref "R15") (pin "2") (pinfunction "2_2") (pintype "passive"))
    )
    (net (code "36") (name "/DATA_28") (class "Default")
      (node (ref "R14") (pin "2") (pinfunction "2_2") (pintype "passive"))
    )
    (net (code "37") (name "/DATA_29") (class "Default")
      (node (ref "R13") (pin "2") (pinfunction "2_2") (pintype "passive"))
    )
    (net (code "38") (name "/DATA_30") (class "Default")
      (node (ref "R12") (pin "2") (pinfunction "2_2") (pintype "passive"))
    )
    (net (code "39") (name "/DATA_31") (class "Default")
      (node (ref "R11") (pin "2") (pinfunction "2_2") (pintype "passive"))
    )
    (net (code "40") (name "/GPIO0") (class "Default")
      (node (ref "R21") (pin "1") (pinfunction "1_1") (pintype "passive"))
    )
    (net (code "41") (name "/GPIO1") (class "Default")
      (node (ref "R22") (pin "1") (pinfunction "1_1") (pintype "passive"))
    )
    (net (code "42") (name "/OE_N") (class "Default")
      (node (ref "R70") (pin "1") (pinfunction "1_1") (pintype "passive"))
    )
    (net (code "43") (name "/RD_N") (class "Default")
      (node (ref "R60") (pin "1") (pinfunction "1_1") (pintype "passive"))
    )
    (net (code "44") (name "/RID+") (class "Default")
      (node (ref "U7") (pin "34") (pinfunction "RIDN_34") (pintype "passive"))
    )
    (net (code "45") (name "/RID-") (class "Default")
      (node (ref "U7") (pin "35") (pinfunction "RIDP_35") (pintype "passive"))
    )
    (net (code "46") (name "/RST_N") (class "Default")
      (node (ref "R19") (pin "1") (pinfunction "1_1") (pintype "passive"))
    )
    (net (code "47") (name "/RXF_N") (class "Default")
      (node (ref "R56") (pin "1") (pinfunction "1_1") (pintype "passive"))
    )
    (net (code "48") (name "/SIWU_N") (class "Default")
      (node (ref "R58") (pin "1") (pinfunction "1_1") (pintype "passive"))
    )
    (net (code "49") (name "/TOD+") (class "Default")
      (node (ref "C49") (pin "1") (pinfunction "1_1") (pintype "passive"))
    )
    (net (code "50") (name "/TOD-") (class "Default")
      (node (ref "C54") (pin "1") (pinfunction "1_1") (pintype "passive"))
    )
    (net (code "51") (name "/TXE_N") (class "Default")
      (node (ref "R54") (pin "1") (pinfunction "1_1") (pintype "passive"))
    )
    (net (code "52") (name "/USB_RX") (class "Default")
      (node (ref "D4") (pin "1") (pinfunction "1_1") (pintype "passive"))
    )
    (net (code "53") (name "/USB_TX") (class "Default")
      (node (ref "D3") (pin "1") (pinfunction "1_1") (pintype "passive"))
    )
    (net (code "54") (name "/WKUP_N") (class "Default")
      (node (ref "R20") (pin "1") (pinfunction "1_1") (pintype "passive"))
    )
    (net (code "55") (name "/WR_N") (class "Default")
      (node (ref "R59") (pin "1") (pinfunction "1_1") (pintype "passive"))
    )
    (net (code "56") (name "3V3") (class "Default")
      (node (ref "C103") (pin "2") (pinfunction "2_2") (pintype "passive"))
      (node (ref "C104") (pin "2") (pinfunction "2_2") (pintype "passive"))
      (node (ref "C42") (pin "1") (pinfunction "1_1") (pintype "passive"))
      (node (ref "C45") (pin "2") (pinfunction "2_2") (pintype "passive"))
      (node (ref "C50") (pin "2") (pinfunction "2_2") (pintype "passive"))
      (node (ref "C51") (pin "2") (pinfunction "2_2") (pintype "passive"))
      (node (ref "C73") (pin "2") (pinfunction "2_2") (pintype "passive"))
      (node (ref "C74") (pin "2") (pinfunction "2_2") (pintype "passive"))
      (node (ref "L8") (pin "1") (pinfunction "1_1") (pintype "passive"))
      (node (ref "R16") (pin "2") (pinfunction "2_2") (pintype "passive"))
      (node (ref "R17") (pin "2") (pinfunction "2_2") (pintype "passive"))
      (node (ref "U7") (pin "14") (pinfunction "VCCIO_14") (pintype "passive"))
      (node (ref "U7") (pin "20") (pinfunction "VCC33_20") (pintype "passive"))
      (node (ref "U7") (pin "49") (pinfunction "VCCIO_49") (pintype "passive"))
      (node (ref "U7") (pin "59") (pinfunction "VCCIO_59") (pintype "passive"))
      (node (ref "U7") (pin "68") (pinfunction "VCCIO_68") (pintype "passive"))
      (node (ref "VR1") (pin "2") (pinfunction "VOUT_2") (pintype "power_in"))
      (node (ref "VR1") (pin "4") (pinfunction "TAB_4") (pintype "passive"))
    )
    (net (code "57") (name "5V") (class "Default")
      (node (ref "C41") (pin "1") (pinfunction "1_1") (pintype "passive"))
      (node (ref "C44") (pin "2") (pinfunction "2_2") (pintype "passive"))
      (node (ref "VR1") (pin "3") (pinfunction "VIN_3") (pintype "power_in"))
    )
    (net (code "58") (name "GND") (class "Default")
      (node (ref "C101") (pin "1") (pinfunction "1_1") (pintype "passive"))
      (node (ref "C102") (pin "1") (pinfunction "1_1") (pintype "passive"))
      (node (ref "C103") (pin "1") (pinfunction "1_1") (pintype "passive"))
      (node (ref "C104") (pin "1") (pinfunction "1_1") (pintype "passive"))
      (node (ref "C166") (pin "1") (pinfunction "1_1") (pintype "passive"))
      (node (ref "C167") (pin "1") (pinfunction "1_1") (pintype "passive"))
      (node (ref "C168") (pin "1") (pinfunction "1_1") (pintype "passive"))
      (node (ref "C169") (pin "1") (pinfunction "1_1") (pintype "passive"))
      (node (ref "C41") (pin "2") (pinfunction "2_2") (pintype "passive"))
      (node (ref "C42") (pin "2") (pinfunction "2_2") (pintype "passive"))
      (node (ref "C43") (pin "2") (pinfunction "2_2") (pintype "passive"))
      (node (ref "C44") (pin "1") (pinfunction "1_1") (pintype "passive"))
      (node (ref "C45") (pin "1") (pinfunction "1_1") (pintype "passive"))
      (node (ref "C46") (pin "1") (pinfunction "1_1") (pintype "passive"))
      (node (ref "C47") (pin "1") (pinfunction "1_1") (pintype "passive"))
      (node (ref "C48") (pin "1") (pinfunction "1_1") (pintype "passive"))
      (node (ref "C50") (pin "1") (pinfunction "1_1") (pintype "passive"))
      (node (ref "C51") (pin "1") (pinfunction "1_1") (pintype "passive"))
      (node (ref "C52") (pin "1") (pinfunction "1_1") (pintype "passive"))
      (node (ref "C53") (pin "1") (pinfunction "1_1") (pintype "passive"))
      (node (ref "C55") (pin "1") (pinfunction "1_1") (pintype "passive"))
      (node (ref "C56") (pin "1") (pinfunction "1_1") (pintype "passive"))
      (node (ref "C57") (pin "1") (pinfunction "1_1") (pintype "passive"))
      (node (ref "C58") (pin "1") (pinfunction "1_1") (pintype "passive"))
      (node (ref "C59") (pin "1") (pinfunction "1_1") (pintype "passive"))
      (node (ref "C60") (pin "1") (pinfunction "1_1") (pintype "passive"))
      (node (ref "C61") (pin "1") (pinfunction "1_1") (pintype "passive"))
      (node (ref "C62") (pin "1") (pinfunction "1_1") (pintype "passive"))
      (node (ref "C73") (pin "1") (pinfunction "1_1") (pintype "passive"))
      (node (ref "C74") (pin "1") (pinfunction "1_1") (pintype "passive"))
      (node (ref "R24") (pin "1") (pinfunction "1_1") (pintype "passive"))
      (node (ref "U7") (pin "1") (pinfunction "GND_1") (pintype "passive"))
      (node (ref "U7") (pin "26") (pinfunction "GND_26") (pintype "passive"))
      (node (ref "U7") (pin "29") (pinfunction "GND_29") (pintype "passive"))
      (node (ref "U7") (pin "36") (pinfunction "GND_36") (pintype "passive"))
      (node (ref "U7") (pin "77") (pinfunction "GND_77") (pintype "passive"))
      (node (ref "VR1") (pin "1") (pinfunction "GND_1") (pintype "power_in"))
      (node (ref "X3") (pin "2") (pinfunction "Gnd_2") (pintype "power_in"))
      (node (ref "X3") (pin "4") (pinfunction "Gnd_4") (pintype "power_in"))
    )
    (net (code "59") (name "Net-(D1-K)") (class "Default")
      (node (ref "D1") (pin "2") (pinfunction "K_2") (pintype "passive"))
      (node (ref "D3") (pin "2") (pinfunction "2_2") (pintype "passive"))
    )
    (net (code "60") (name "Net-(D2-K)") (class "Default")
      (node (ref "D2") (pin "2") (pinfunction "K_2") (pintype "passive"))
      (node (ref "D4") (pin "2") (pinfunction "2_2") (pintype "passive"))
    )
    (net (code "61") (name "Net-(U7-BE_0)") (class "Default")
      (node (ref "R46") (pin "2") (pinfunction "2_2") (pintype "passive"))
      (node (ref "U7") (pin "4") (pinfunction "BE_0_4") (pintype "passive"))
    )
    (net (code "62") (name "Net-(U7-BE_1)") (class "Default")
      (node (ref "R48") (pin "2") (pinfunction "2_2") (pintype "passive"))
      (node (ref "U7") (pin "5") (pinfunction "BE_1_5") (pintype "passive"))
    )
    (net (code "63") (name "Net-(U7-BE_2)") (class "Default")
      (node (ref "R50") (pin "2") (pinfunction "2_2") (pintype "passive"))
      (node (ref "U7") (pin "6") (pinfunction "BE_2_6") (pintype "passive"))
    )
    (net (code "64") (name "Net-(U7-BE_3)") (class "Default")
      (node (ref "R52") (pin "2") (pinfunction "2_2") (pintype "passive"))
      (node (ref "U7") (pin "7") (pinfunction "BE_3_7") (pintype "passive"))
    )
    (net (code "65") (name "Net-(U7-CLK)") (class "Default")
      (node (ref "R43") (pin "1") (pinfunction "1_1") (pintype "passive"))
      (node (ref "U7") (pin "58") (pinfunction "CLK_58") (pintype "passive"))
    )
    (net (code "66") (name "Net-(U7-DATA_0)") (class "Default")
      (node (ref "R77") (pin "1") (pinfunction "1_1") (pintype "passive"))
      (node (ref "U7") (pin "40") (pinfunction "DATA_0_40") (pintype "passive"))
    )
    (net (code "67") (name "Net-(U7-DATA_1)") (class "Default")
      (node (ref "R76") (pin "1") (pinfunction "1_1") (pintype "passive"))
      (node (ref "U7") (pin "41") (pinfunction "DATA_1_41") (pintype "passive"))
    )
    (net (code "68") (name "Net-(U7-DATA_2)") (class "Default")
      (node (ref "R75") (pin "1") (pinfunction "1_1") (pintype "passive"))
      (node (ref "U7") (pin "42") (pinfunction "DATA_2_42") (pintype "passive"))
    )
    (net (code "69") (name "Net-(U7-DATA_3)") (class "Default")
      (node (ref "R74") (pin "1") (pinfunction "1_1") (pintype "passive"))
      (node (ref "U7") (pin "43") (pinfunction "DATA_3_43") (pintype "passive"))
    )
    (net (code "70") (name "Net-(U7-DATA_4)") (class "Default")
      (node (ref "R73") (pin "1") (pinfunction "1_1") (pintype "passive"))
      (node (ref "U7") (pin "44") (pinfunction "DATA_4_44") (pintype "passive"))
    )
    (net (code "71") (name "Net-(U7-DATA_5)") (class "Default")
      (node (ref "R72") (pin "1") (pinfunction "1_1") (pintype "passive"))
      (node (ref "U7") (pin "45") (pinfunction "DATA_5_45") (pintype "passive"))
    )
    (net (code "72") (name "Net-(U7-DATA_6)") (class "Default")
      (node (ref "R71") (pin "1") (pinfunction "1_1") (pintype "passive"))
      (node (ref "U7") (pin "46") (pinfunction "DATA_6_46") (pintype "passive"))
    )
    (net (code "73") (name "Net-(U7-DATA_7)") (class "Default")
      (node (ref "R61") (pin "1") (pinfunction "1_1") (pintype "passive"))
      (node (ref "U7") (pin "47") (pinfunction "DATA_7_47") (pintype "passive"))
    )
    (net (code "74") (name "Net-(U7-DATA_8)") (class "Default")
      (node (ref "R57") (pin "1") (pinfunction "1_1") (pintype "passive"))
      (node (ref "U7") (pin "50") (pinfunction "DATA_8_50") (pintype "passive"))
    )
    (net (code "75") (name "Net-(U7-DATA_9)") (class "Default")
      (node (ref "R55") (pin "1") (pinfunction "1_1") (pintype "passive"))
      (node (ref "U7") (pin "51") (pinfunction "DATA_9_51") (pintype "passive"))
    )
    (net (code "76") (name "Net-(U7-DATA_10)") (class "Default")
      (node (ref "R53") (pin "1") (pinfunction "1_1") (pintype "passive"))
      (node (ref "U7") (pin "52") (pinfunction "DATA_10_52") (pintype "passive"))
    )
    (net (code "77") (name "Net-(U7-DATA_11)") (class "Default")
      (node (ref "R51") (pin "1") (pinfunction "1_1") (pintype "passive"))
      (node (ref "U7") (pin "53") (pinfunction "DATA_11_53") (pintype "passive"))
    )
    (net (code "78") (name "Net-(U7-DATA_12)") (class "Default")
      (node (ref "R49") (pin "1") (pinfunction "1_1") (pintype "passive"))
      (node (ref "U7") (pin "54") (pinfunction "DATA_12_54") (pintype "passive"))
    )
    (net (code "79") (name "Net-(U7-DATA_13)") (class "Default")
      (node (ref "R47") (pin "1") (pinfunction "1_1") (pintype "passive"))
      (node (ref "U7") (pin "55") (pinfunction "DATA_13_55") (pintype "passive"))
    )
    (net (code "80") (name "Net-(U7-DATA_14)") (class "Default")
      (node (ref "R45") (pin "1") (pinfunction "1_1") (pintype "passive"))
      (node (ref "U7") (pin "56") (pinfunction "DATA_14_56") (pintype "passive"))
    )
    (net (code "81") (name "Net-(U7-DATA_15)") (class "Default")
      (node (ref "R44") (pin "1") (pinfunction "1_1") (pintype "passive"))
      (node (ref "U7") (pin "57") (pinfunction "DATA_15_57") (pintype "passive"))
    )
    (net (code "82") (name "Net-(U7-DATA_16)") (class "Default")
      (node (ref "R42") (pin "1") (pinfunction "1_1") (pintype "passive"))
      (node (ref "U7") (pin "60") (pinfunction "DATA_16_60") (pintype "passive"))
    )
    (net (code "83") (name "Net-(U7-DATA_17)") (class "Default")
      (node (ref "R41") (pin "1") (pinfunction "1_1") (pintype "passive"))
      (node (ref "U7") (pin "61") (pinfunction "DATA_17_61") (pintype "passive"))
    )
    (net (code "84") (name "Net-(U7-DATA_18)") (class "Default")
      (node (ref "R40") (pin "1") (pinfunction "1_1") (pintype "passive"))
      (node (ref "U7") (pin "62") (pinfunction "DATA_18_62") (pintype "passive"))
    )
    (net (code "85") (name "Net-(U7-DATA_19)") (class "Default")
      (node (ref "R39") (pin "1") (pinfunction "1_1") (pintype "passive"))
      (node (ref "U7") (pin "63") (pinfunction "DATA_19_63") (pintype "passive"))
    )
    (net (code "86") (name "Net-(U7-DATA_20)") (class "Default")
      (node (ref "R38") (pin "1") (pinfunction "1_1") (pintype "passive"))
      (node (ref "U7") (pin "64") (pinfunction "DATA_20_64") (pintype "passive"))
    )
    (net (code "87") (name "Net-(U7-DATA_21)") (class "Default")
      (node (ref "R37") (pin "1") (pinfunction "1_1") (pintype "passive"))
      (node (ref "U7") (pin "65") (pinfunction "DATA_21_65") (pintype "passive"))
    )
    (net (code "88") (name "Net-(U7-DATA_22)") (class "Default")
      (node (ref "R36") (pin "1") (pinfunction "1_1") (pintype "passive"))
      (node (ref "U7") (pin "66") (pinfunction "DATA_22_66") (pintype "passive"))
    )
    (net (code "89") (name "Net-(U7-DATA_23)") (class "Default")
      (node (ref "R35") (pin "1") (pinfunction "1_1") (pintype "passive"))
      (node (ref "U7") (pin "67") (pinfunction "DATA_23_67") (pintype "passive"))
    )
    (net (code "90") (name "Net-(U7-DATA_24)") (class "Default")
      (node (ref "R34") (pin "1") (pinfunction "1_1") (pintype "passive"))
      (node (ref "U7") (pin "69") (pinfunction "DATA_24_69") (pintype "passive"))
    )
    (net (code "91") (name "Net-(U7-DATA_25)") (class "Default")
      (node (ref "R25") (pin "1") (pinfunction "1_1") (pintype "passive"))
      (node (ref "U7") (pin "70") (pinfunction "DATA_25_70") (pintype "passive"))
    )
    (net (code "92") (name "Net-(U7-DATA_26)") (class "Default")
      (node (ref "R18") (pin "1") (pinfunction "1_1") (pintype "passive"))
      (node (ref "U7") (pin "71") (pinfunction "DATA_26_71") (pintype "passive"))
    )
    (net (code "93") (name "Net-(U7-DATA_27)") (class "Default")
      (node (ref "R15") (pin "1") (pinfunction "1_1") (pintype "passive"))
      (node (ref "U7") (pin "72") (pinfunction "DATA_27_72") (pintype "passive"))
    )
    (net (code "94") (name "Net-(U7-DATA_28)") (class "Default")
      (node (ref "R14") (pin "1") (pinfunction "1_1") (pintype "passive"))
      (node (ref "U7") (pin "73") (pinfunction "DATA_28_73") (pintype "passive"))
    )
    (net (code "95") (name "Net-(U7-DATA_29)") (class "Default")
      (node (ref "R13") (pin "1") (pinfunction "1_1") (pintype "passive"))
      (node (ref "U7") (pin "74") (pinfunction "DATA_29_74") (pintype "passive"))
    )
    (net (code "96") (name "Net-(U7-DATA_30)") (class "Default")
      (node (ref "R12") (pin "1") (pinfunction "1_1") (pintype "passive"))
      (node (ref "U7") (pin "75") (pinfunction "DATA_30_75") (pintype "passive"))
    )
    (net (code "97") (name "Net-(U7-DATA_31)") (class "Default")
      (node (ref "R11") (pin "1") (pinfunction "1_1") (pintype "passive"))
      (node (ref "U7") (pin "76") (pinfunction "DATA_31_76") (pintype "passive"))
    )
    (net (code "98") (name "Net-(U7-GPIO0)") (class "Default")
      (node (ref "R21") (pin "2") (pinfunction "2_2") (pintype "passive"))
      (node (ref "U7") (pin "17") (pinfunction "GPIO0_17") (pintype "passive"))
    )
    (net (code "99") (name "Net-(U7-GPIO1)") (class "Default")
      (node (ref "R22") (pin "2") (pinfunction "2_2") (pintype "passive"))
      (node (ref "U7") (pin "18") (pinfunction "GPIO1_18") (pintype "passive"))
    )
    (net (code "100") (name "Net-(U7-OE_N)") (class "Default")
      (node (ref "R70") (pin "2") (pinfunction "2_2") (pintype "passive"))
      (node (ref "U7") (pin "13") (pinfunction "OE_N_13") (pintype "passive"))
    )
    (net (code "101") (name "Net-(U7-RD_N)") (class "Default")
      (node (ref "R60") (pin "2") (pinfunction "2_2") (pintype "passive"))
      (node (ref "U7") (pin "12") (pinfunction "RD_N_12") (pintype "passive"))
    )
    (net (code "102") (name "Net-(U7-RESET_N)") (class "Default")
      (node (ref "C48") (pin "2") (pinfunction "2_2") (pintype "passive"))
      (node (ref "R17") (pin "1") (pinfunction "1_1") (pintype "passive"))
      (node (ref "R19") (pin "2") (pinfunction "2_2") (pintype "passive"))
      (node (ref "U7") (pin "15") (pinfunction "RESET_N_15") (pintype "passive"))
    )
    (net (code "103") (name "Net-(U7-RREF)") (class "Default")
      (node (ref "R24") (pin "2") (pinfunction "2_2") (pintype "passive"))
      (node (ref "U7") (pin "27") (pinfunction "RREF_27") (pintype "passive"))
    )
    (net (code "104") (name "Net-(U7-RXF_N)") (class "Default")
      (node (ref "R56") (pin "2") (pinfunction "2_2") (pintype "passive"))
      (node (ref "U7") (pin "9") (pinfunction "RXF_N_9") (pintype "passive"))
    )
    (net (code "105") (name "Net-(U7-SIWU_N)") (class "Default")
      (node (ref "R58") (pin "2") (pinfunction "2_2") (pintype "passive"))
      (node (ref "U7") (pin "10") (pinfunction "SIWU_N_10") (pintype "passive"))
    )
    (net (code "106") (name "Net-(U7-TODN)") (class "Default")
      (node (ref "C54") (pin "2") (pinfunction "2_2") (pintype "passive"))
      (node (ref "U7") (pin "31") (pinfunction "TODN_31") (pintype "passive"))
    )
    (net (code "107") (name "Net-(U7-TODP)") (class "Default")
      (node (ref "C49") (pin "2") (pinfunction "2_2") (pintype "passive"))
      (node (ref "U7") (pin "32") (pinfunction "TODP_32") (pintype "passive"))
    )
    (net (code "108") (name "Net-(U7-TXE_N)") (class "Default")
      (node (ref "R54") (pin "2") (pinfunction "2_2") (pintype "passive"))
      (node (ref "U7") (pin "8") (pinfunction "TXE_N_8") (pintype "passive"))
    )
    (net (code "109") (name "Net-(U7-VBUS)") (class "Default")
      (node (ref "R23") (pin "1") (pinfunction "1_1") (pintype "passive"))
      (node (ref "U7") (pin "37") (pinfunction "VBUS_37") (pintype "passive"))
    )
    (net (code "110") (name "Net-(U7-WAKEUP_N)") (class "Default")
      (node (ref "R16") (pin "1") (pinfunction "1_1") (pintype "passive"))
      (node (ref "R20") (pin "2") (pinfunction "2_2") (pintype "passive"))
      (node (ref "U7") (pin "16") (pinfunction "WAKEUP_N_16") (pintype "passive"))
    )
    (net (code "111") (name "Net-(U7-WR_N)") (class "Default")
      (node (ref "R59") (pin "2") (pinfunction "2_2") (pintype "passive"))
      (node (ref "U7") (pin "11") (pinfunction "WR_N_11") (pintype "passive"))
    )
    (net (code "112") (name "Net-(U7-XI)") (class "Default")
      (node (ref "C52") (pin "2") (pinfunction "2_2") (pintype "passive"))
      (node (ref "U7") (pin "21") (pinfunction "XI_21") (pintype "passive"))
      (node (ref "X3") (pin "1") (pinfunction "1_1") (pintype "passive"))
    )
    (net (code "113") (name "Net-(U7-XO)") (class "Default")
      (node (ref "C53") (pin "2") (pinfunction "2_2") (pintype "passive"))
      (node (ref "U7") (pin "22") (pinfunction "XO_22") (pintype "passive"))
      (node (ref "X3") (pin "3") (pinfunction "3_3") (pintype "passive"))
    )
    (net (code "114") (name "VBUS") (class "Default")
      (node (ref "R23") (pin "2") (pinfunction "2_2") (pintype "passive"))
    )
    (net (code "115") (name "VCC33") (class "Default")
      (node (ref "C43") (pin "1") (pinfunction "1_1") (pintype "passive"))
      (node (ref "C46") (pin "2") (pinfunction "2_2") (pintype "passive"))
      (node (ref "C47") (pin "2") (pinfunction "2_2") (pintype "passive"))
      (node (ref "C55") (pin "2") (pinfunction "2_2") (pintype "passive"))
      (node (ref "C56") (pin "2") (pinfunction "2_2") (pintype "passive"))
      (node (ref "C57") (pin "2") (pinfunction "2_2") (pintype "passive"))
      (node (ref "C58") (pin "2") (pinfunction "2_2") (pintype "passive"))
      (node (ref "D1") (pin "1") (pinfunction "A_1") (pintype "passive"))
      (node (ref "D2") (pin "1") (pinfunction "A_1") (pintype "passive"))
      (node (ref "L8") (pin "2") (pinfunction "2_2") (pintype "passive"))
      (node (ref "U7") (pin "24") (pinfunction "VCC33_24") (pintype "passive"))
      (node (ref "U7") (pin "28") (pinfunction "VDDA_28") (pintype "passive"))
      (node (ref "U7") (pin "38") (pinfunction "VCC33_38") (pintype "passive"))
    )
    (net (code "116") (name "VD10") (class "Default")
      (node (ref "C101") (pin "2") (pinfunction "2_2") (pintype "passive"))
      (node (ref "C102") (pin "2") (pinfunction "2_2") (pintype "passive"))
      (node (ref "C166") (pin "2") (pinfunction "2_2") (pintype "passive"))
      (node (ref "C167") (pin "2") (pinfunction "2_2") (pintype "passive"))
      (node (ref "C168") (pin "2") (pinfunction "2_2") (pintype "passive"))
      (node (ref "C169") (pin "2") (pinfunction "2_2") (pintype "passive"))
      (node (ref "C59") (pin "2") (pinfunction "2_2") (pintype "passive"))
      (node (ref "C60") (pin "2") (pinfunction "2_2") (pintype "passive"))
      (node (ref "C61") (pin "2") (pinfunction "2_2") (pintype "passive"))
      (node (ref "C62") (pin "2") (pinfunction "2_2") (pintype "passive"))
      (node (ref "U7") (pin "2") (pinfunction "AVDD_2") (pintype "passive"))
      (node (ref "U7") (pin "3") (pinfunction "VD10_3") (pintype "passive"))
      (node (ref "U7") (pin "30") (pinfunction "VD10_30") (pintype "passive"))
      (node (ref "U7") (pin "33") (pinfunction "VD10_33") (pintype "passive"))
      (node (ref "U7") (pin "39") (pinfunction "DV10_39") (pintype "passive"))
      (node (ref "U7") (pin "48") (pinfunction "VD10_48") (pintype "passive"))
    )
    (net (code "117") (name "unconnected-(U7-RESERVED-Pad19)") (class "Default")
      (node (ref "U7") (pin "19") (pinfunction "RESERVED_19") (pintype "passive+no_connect"))
    )
  )
)
